# mainCircuit.net
KiCad netlist of a schematic drawn in EAGLE
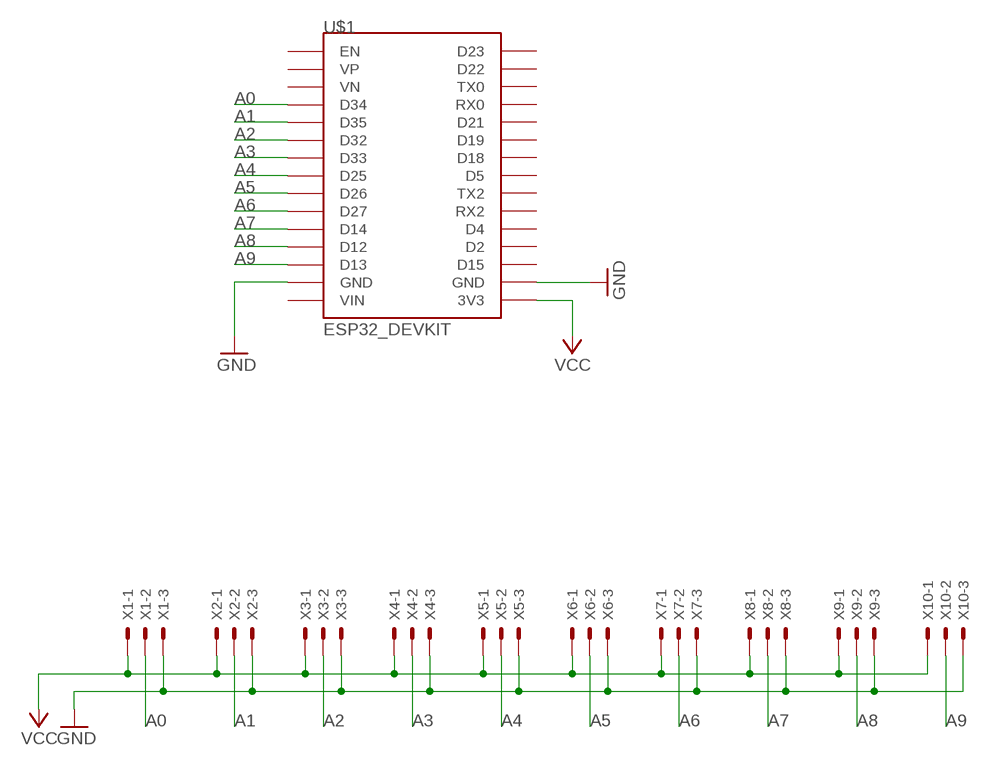
[diagram p0: schematic, sheet 1]

(export (version "E")
  (design (tool "Eeschema 10.0.6"))
  (components
    (comp (ref "U$1")
      (value "ESP32_DEVKIT")
      (footprint "eagle-import:ESP32_DEVKIT")
      (libsource (lib "eagle-import") (part "ESP32_DEVKIT"))
    )
    (comp (ref "X1")
      (value "JST-XH-03-PIN-LONG-PAD")
      (footprint "eagle-import:JST-XH-03-PACKAGE-LONG-PAD")
      (libsource (lib "eagle-import") (part "JST-XH-03-PIN-LONG-PAD"))
    )
    (comp (ref "X2")
      (value "JST-XH-03-PIN-LONG-PAD")
      (footprint "eagle-import:JST-XH-03-PACKAGE-LONG-PAD")
      (libsource (lib "eagle-import") (part "JST-XH-03-PIN-LONG-PAD"))
    )
    (comp (ref "X3")
      (value "JST-XH-03-PIN-LONG-PAD")
      (footprint "eagle-import:JST-XH-03-PACKAGE-LONG-PAD")
      (libsource (lib "eagle-import") (part "JST-XH-03-PIN-LONG-PAD"))
    )
    (comp (ref "X4")
      (value "JST-XH-03-PIN-LONG-PAD")
      (footprint "eagle-import:JST-XH-03-PACKAGE-LONG-PAD")
      (libsource (lib "eagle-import") (part "JST-XH-03-PIN-LONG-PAD"))
    )
    (comp (ref "X5")
      (value "JST-XH-03-PIN-LONG-PAD")
      (footprint "eagle-import:JST-XH-03-PACKAGE-LONG-PAD")
      (libsource (lib "eagle-import") (part "JST-XH-03-PIN-LONG-PAD"))
    )
    (comp (ref "X6")
      (value "JST-XH-03-PIN-LONG-PAD")
      (footprint "eagle-import:JST-XH-03-PACKAGE-LONG-PAD")
      (libsource (lib "eagle-import") (part "JST-XH-03-PIN-LONG-PAD"))
    )
    (comp (ref "X7")
      (value "JST-XH-03-PIN-LONG-PAD")
      (footprint "eagle-import:JST-XH-03-PACKAGE-LONG-PAD")
      (libsource (lib "eagle-import") (part "JST-XH-03-PIN-LONG-PAD"))
    )
    (comp (ref "X8")
      (value "JST-XH-03-PIN-LONG-PAD")
      (footprint "eagle-import:JST-XH-03-PACKAGE-LONG-PAD")
      (libsource (lib "eagle-import") (part "JST-XH-03-PIN-LONG-PAD"))
    )
    (comp (ref "X9")
      (value "JST-XH-03-PIN-LONG-PAD")
      (footprint "eagle-import:JST-XH-03-PACKAGE-LONG-PAD")
      (libsource (lib "eagle-import") (part "JST-XH-03-PIN-LONG-PAD"))
    )
    (comp (ref "X10")
      (value "JST-XH-03-PIN-LONG-PAD")
      (footprint "eagle-import:JST-XH-03-PACKAGE-LONG-PAD")
      (libsource (lib "eagle-import") (part "JST-XH-03-PIN-LONG-PAD"))
    )
  )
  (nets
    (net (code "1") (name "/A0") (class "Default")
      (node (ref "U$1") (pin "D34") (pinfunction "D34_D34") (pintype "bidirectional"))
      (node (ref "X1") (pin "2") (pinfunction "S_2") (pintype "passive"))
    )
    (net (code "2") (name "/A1") (class "Default")
      (node (ref "U$1") (pin "D35") (pinfunction "D35_D35") (pintype "bidirectional"))
      (node (ref "X2") (pin "2") (pinfunction "S_2") (pintype "passive"))
    )
    (net (code "3") (name "/A2") (class "Default")
      (node (ref "U$1") (pin "D32") (pinfunction "D32_D32") (pintype "bidirectional"))
      (node (ref "X3") (pin "2") (pinfunction "S_2") (pintype "passive"))
    )
    (net (code "4") (name "/A3") (class "Default")
      (node (ref "U$1") (pin "D33") (pinfunction "D33_D33") (pintype "bidirectional"))
      (node (ref "X4") (pin "2") (pinfunction "S_2") (pintype "passive"))
    )
    (net (code "5") (name "/A4") (class "Default")
      (node (ref "U$1") (pin "D25") (pinfunction "D25_D25") (pintype "bidirectional"))
      (node (ref "X5") (pin "2") (pinfunction "S_2") (pintype "passive"))
    )
    (net (code "6") (name "/A5") (class "Default")
      (node (ref "U$1") (pin "D26") (pinfunction "D26_D26") (pintype "bidirectional"))
      (node (ref "X6") (pin "2") (pinfunction "S_2") (pintype "passive"))
    )
    (net (code "7") (name "/A6") (class "Default")
      (node (ref "U$1") (pin "D27") (pinfunction "D27_D27") (pintype "bidirectional"))
      (node (ref "X7") (pin "2") (pinfunction "S_2") (pintype "passive"))
    )
    (net (code "8") (name "/A7") (class "Default")
      (node (ref "U$1") (pin "D14") (pinfunction "D14_D14") (pintype "bidirectional"))
      (node (ref "X8") (pin "2") (pinfunction "S_2") (pintype "passive"))
    )
    (net (code "9") (name "/A8") (class "Default")
      (node (ref "U$1") (pin "D12") (pinfunction "D12_D12") (pintype "bidirectional"))
      (node (ref "X9") (pin "2") (pinfunction "S_2") (pintype "passive"))
    )
    (net (code "10") (name "/A9") (class "Default")
      (node (ref "U$1") (pin "D13") (pinfunction "D13_D13") (pintype "bidirectional"))
      (node (ref "X10") (pin "2") (pinfunction "S_2") (pintype "passive"))
    )
    (net (code "11") (name "GND") (class "Default")
      (node (ref "U$1") (pin "GND@1") (pinfunction "GND_GND@1") (pintype "bidirectional"))
      (node (ref "U$1") (pin "GND@2") (pinfunction "GND_GND@2") (pintype "bidirectional"))
      (node (ref "X1") (pin "3") (pinfunction "S_3") (pintype "passive"))
      (node (ref "X10") (pin "3") (pinfunction "S_3") (pintype "passive"))
      (node (ref "X2") (pin "3") (pinfunction "S_3") (pintype "passive"))
      (node (ref "X3") (pin "3") (pinfunction "S_3") (pintype "passive"))
      (node (ref "X4") (pin "3") (pinfunction "S_3") (pintype "passive"))
      (node (ref "X5") (pin "3") (pinfunction "S_3") (pintype "passive"))
      (node (ref "X6") (pin "3") (pinfunction "S_3") (pintype "passive"))
      (node (ref "X7") (pin "3") (pinfunction "S_3") (pintype "passive"))
      (node (ref "X8") (pin "3") (pinfunction "S_3") (pintype "passive"))
      (node (ref "X9") (pin "3") (pinfunction "S_3") (pintype "passive"))
    )
    (net (code "12") (name "VCC") (class "Default")
      (node (ref "U$1") (pin "3V3") (pinfunction "3V3_3V3") (pintype "bidirectional"))
      (node (ref "X1") (pin "1") (pinfunction "S_1") (pintype "passive"))
      (node (ref "X10") (pin "1") (pinfunction "S_1") (pintype "passive"))
      (node (ref "X2") (pin "1") (pinfunction "S_1") (pintype "passive"))
      (node (ref "X3") (pin "1") (pinfunction "S_1") (pintype "passive"))
      (node (ref "X4") (pin "1") (pinfunction "S_1") (pintype "passive"))
      (node (ref "X5") (pin "1") (pinfunction "S_1") (pintype "passive"))
      (node (ref "X6") (pin "1") (pinfunction "S_1") (pintype "passive"))
      (node (ref "X7") (pin "1") (pinfunction "S_1") (pintype "passive"))
      (node (ref "X8") (pin "1") (pinfunction "S_1") (pintype "passive"))
      (node (ref "X9") (pin "1") (pinfunction "S_1") (pintype "passive"))
    )
    (net (code "13") (name "unconnected-(U$1-PadD2)") (class "Default")
      (node (ref "U$1") (pin "D2") (pinfunction "D2_D2") (pintype "bidirectional"))
    )
    (net (code "14") (name "unconnected-(U$1-PadD4)") (class "Default")
      (node (ref "U$1") (pin "D4") (pinfunction "D4_D4") (pintype "bidirectional"))
    )
    (net (code "15") (name "unconnected-(U$1-PadD5)") (class "Default")
      (node (ref "U$1") (pin "D5") (pinfunction "D5_D5") (pintype "bidirectional"))
    )
    (net (code "16") (name "unconnected-(U$1-PadD15)") (class "Default")
      (node (ref "U$1") (pin "D15") (pinfunction "D15_D15") (pintype "bidirectional"))
    )
    (net (code "17") (name "unconnected-(U$1-PadD18)") (class "Default")
      (node (ref "U$1") (pin "D18") (pinfunction "D18_D18") (pintype "bidirectional"))
    )
    (net (code "18") (name "unconnected-(U$1-PadD19)") (class "Default")
      (node (ref "U$1") (pin "D19") (pinfunction "D19_D19") (pintype "bidirectional"))
    )
    (net (code "19") (name "unconnected-(U$1-PadD21)") (class "Default")
      (node (ref "U$1") (pin "D21") (pinfunction "D21_D21") (pintype "bidirectional"))
    )
    (net (code "20") (name "unconnected-(U$1-PadD22)") (class "Default")
      (node (ref "U$1") (pin "D22") (pinfunction "D22_D22") (pintype "bidirectional"))
    )
    (net (code "21") (name "unconnected-(U$1-PadD23)") (class "Default")
      (node (ref "U$1") (pin "D23") (pinfunction "D23_D23") (pintype "bidirectional"))
    )
    (net (code "22") (name "unconnected-(U$1-PadEN)") (class "Default")
      (node (ref "U$1") (pin "EN") (pinfunction "EN_EN") (pintype "bidirectional"))
    )
    (net (code "23") (name "unconnected-(U$1-PadRX0)") (class "Default")
      (node (ref "U$1") (pin "RX0") (pinfunction "RX0_RX0") (pintype "bidirectional"))
    )
    (net (code "24") (name "unconnected-(U$1-PadRX2)") (class "Default")
      (node (ref "U$1") (pin "RX2") (pinfunction "RX2_RX2") (pintype "bidirectional"))
    )
    (net (code "25") (name "unconnected-(U$1-PadTX0)") (class "Default")
      (node (ref "U$1") (pin "TX0") (pinfunction "TX0_TX0") (pintype "bidirectional"))
    )
    (net (code "26") (name "unconnected-(U$1-PadTX2)") (class "Default")
      (node (ref "U$1") (pin "TX2") (pinfunction "TX2_TX2") (pintype "bidirectional"))
    )
    (net (code "27") (name "unconnected-(U$1-PadVIN)") (class "Default")
      (node (ref "U$1") (pin "VIN") (pinfunction "VIN_VIN") (pintype "bidirectional"))
    )
    (net (code "28") (name "unconnected-(U$1-PadVN)") (class "Default")
      (node (ref "U$1") (pin "VN") (pinfunction "VN_VN") (pintype "bidirectional"))
    )
    (net (code "29") (name "unconnected-(U$1-PadVP)") (class "Default")
      (node (ref "U$1") (pin "VP") (pinfunction "VP_VP") (pintype "bidirectional"))
    )
  )
)
